# I2C.net
KiCad netlist of a schematic drawn in Altium Designer
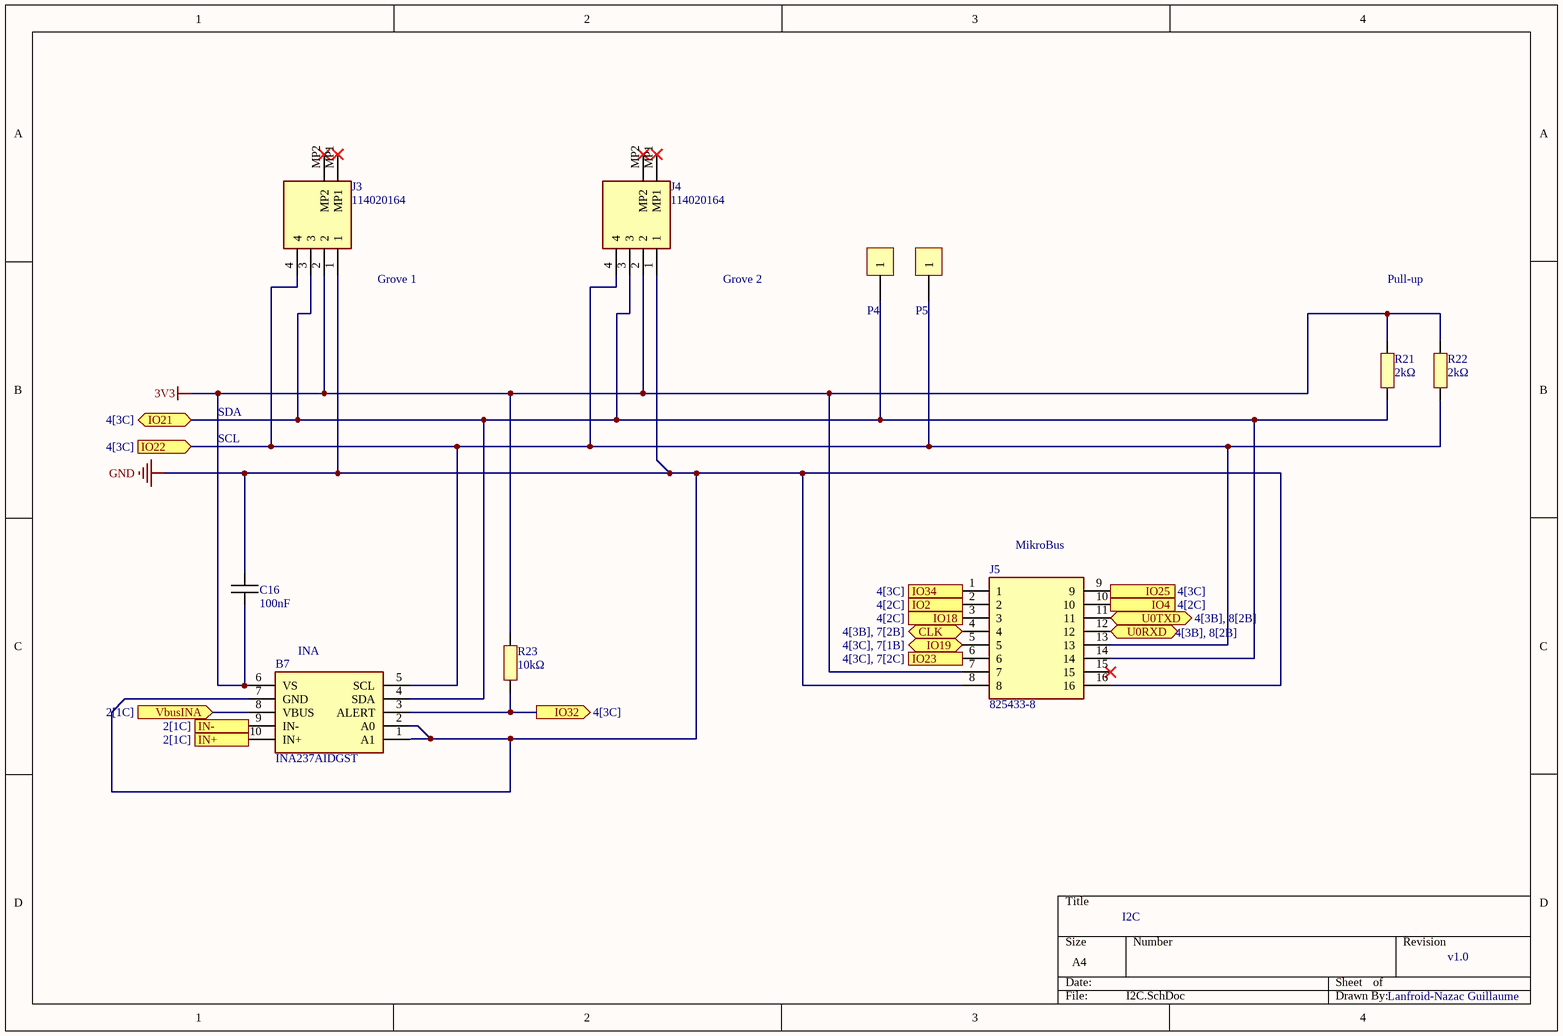
[diagram p0: I2C.SchDoc]

(export (version "E")
  (design (tool "Eeschema 10.0.6"))
  (components
    (comp (ref "B7")
      (value "INA237AIDGST")
      (footprint "SOP50P490X110-10N")
      (fields (field (name "MOUSER PART NUMBER") "595-INA237AIDGST"))
      (libsource (lib "SCHLibrary") (part "INA237AIDGST"))
    )
    (comp (ref "C16")
      (value "100nF")
      (footprint "CAPC1005X06N")
      (libsource (lib "SCHLibrary") (part "Capacitor"))
    )
    (comp (ref "J3")
      (value "114020164")
      (footprint "114020164")
      (description "Seeed Studio Accessories Grove Female Header - SMD-4P-2.0mm-90D-20Pcs")
      (fields (field (name "MOUSER PART NUMBER") "713-114020164"))
      (libsource (lib "SCHLibrary") (part "114020164"))
    )
    (comp (ref "J4")
      (value "114020164")
      (footprint "114020164")
      (description "Seeed Studio Accessories Grove Female Header - SMD-4P-2.0mm-90D-20Pcs")
      (fields (field (name "MOUSER PART NUMBER") "713-114020164"))
      (libsource (lib "SCHLibrary") (part "114020164"))
    )
    (comp (ref "J5")
      (value "825433-8")
      (footprint "Connect-Mikrobus")
      (description "Headers & Wire Housings 8P double for connection mikrobus")
      (fields (field (name "MOUSER PART NUMBER") "571-825433-8"))
      (libsource (lib "SCHLibrary") (part "Connect-Mikrobus"))
    )
    (comp (ref "P4")
      (value "Plage CMS 10x5")
      (footprint "Plage CMS 10x5")
      (description "Plage de report CMS 10x5mm")
      (libsource (lib "SCHLibrary") (part "Plage CMS 10x5"))
    )
    (comp (ref "P5")
      (value "Plage CMS 10x5")
      (footprint "Plage CMS 10x5")
      (description "Plage de report CMS 10x5mm")
      (libsource (lib "SCHLibrary") (part "Plage CMS 10x5"))
    )
    (comp (ref "R21")
      (value "2kΩ")
      (footprint "RESC1005X06N")
      (libsource (lib "SCHLibrary") (part "Resistor"))
    )
    (comp (ref "R22")
      (value "2kΩ")
      (footprint "RESC1005X06N")
      (libsource (lib "SCHLibrary") (part "Resistor"))
    )
    (comp (ref "R23")
      (value "10kΩ")
      (footprint "RESC1005X06N")
      (libsource (lib "SCHLibrary") (part "Resistor"))
    )
  )
  (nets
    (net (code "1") (name "/CLK") (class "Default")
      (node (ref "J5") (pin "4") (pinfunction "4_4") (pintype "passive"))
    )
    (net (code "2") (name "/IN+") (class "Default")
      (node (ref "B7") (pin "10") (pinfunction "IN+_10") (pintype "passive"))
    )
    (net (code "3") (name "/IN-") (class "Default")
      (node (ref "B7") (pin "9") (pinfunction "IN-_9") (pintype "passive"))
    )
    (net (code "4") (name "/IO2") (class "Default")
      (node (ref "J5") (pin "2") (pinfunction "2_2") (pintype "passive"))
    )
    (net (code "5") (name "/IO4") (class "Default")
      (node (ref "J5") (pin "10") (pinfunction "10_10") (pintype "passive"))
    )
    (net (code "6") (name "/IO18") (class "Default")
      (node (ref "J5") (pin "3") (pinfunction "3_3") (pintype "passive"))
    )
    (net (code "7") (name "/IO19") (class "Default")
      (node (ref "J5") (pin "5") (pinfunction "5_5") (pintype "passive"))
    )
    (net (code "8") (name "/IO21") (class "Default")
      (node (ref "B7") (pin "4") (pinfunction "SDA_4") (pintype "passive"))
      (node (ref "J3") (pin "3") (pinfunction "3_3") (pintype "passive"))
      (node (ref "J4") (pin "3") (pinfunction "3_3") (pintype "passive"))
      (node (ref "J5") (pin "14") (pinfunction "14_14") (pintype "passive"))
      (node (ref "P4") (pin "1") (pinfunction "1_1") (pintype "passive"))
      (node (ref "R21") (pin "2") (pinfunction "2_2") (pintype "passive"))
    )
    (net (code "9") (name "/IO22") (class "Default")
      (node (ref "B7") (pin "5") (pinfunction "SCL_5") (pintype "passive"))
      (node (ref "J3") (pin "4") (pinfunction "4_4") (pintype "passive"))
      (node (ref "J4") (pin "4") (pinfunction "4_4") (pintype "passive"))
      (node (ref "J5") (pin "13") (pinfunction "13_13") (pintype "passive"))
      (node (ref "P5") (pin "1") (pinfunction "1_1") (pintype "passive"))
      (node (ref "R22") (pin "2") (pinfunction "2_2") (pintype "passive"))
    )
    (net (code "10") (name "/IO23") (class "Default")
      (node (ref "J5") (pin "6") (pinfunction "6_6") (pintype "passive"))
    )
    (net (code "11") (name "/IO25") (class "Default")
      (node (ref "J5") (pin "9") (pinfunction "9_9") (pintype "passive"))
    )
    (net (code "12") (name "/IO32") (class "Default")
      (node (ref "B7") (pin "3") (pinfunction "ALERT_3") (pintype "passive"))
      (node (ref "R23") (pin "2") (pinfunction "2_2") (pintype "passive"))
    )
    (net (code "13") (name "/IO34") (class "Default")
      (node (ref "J5") (pin "1") (pinfunction "1_1") (pintype "passive"))
    )
    (net (code "14") (name "/U0RXD") (class "Default")
      (node (ref "J5") (pin "12") (pinfunction "12_12") (pintype "passive"))
    )
    (net (code "15") (name "/U0TXD") (class "Default")
      (node (ref "J5") (pin "11") (pinfunction "11_11") (pintype "passive"))
    )
    (net (code "16") (name "/VbusINA") (class "Default")
      (node (ref "B7") (pin "8") (pinfunction "VBUS_8") (pintype "passive"))
    )
    (net (code "17") (name "3V3") (class "Default")
      (node (ref "B7") (pin "6") (pinfunction "VS_6") (pintype "passive"))
      (node (ref "C16") (pin "1") (pinfunction "1_1") (pintype "passive"))
      (node (ref "J3") (pin "2") (pinfunction "2_2") (pintype "passive"))
      (node (ref "J4") (pin "2") (pinfunction "2_2") (pintype "passive"))
      (node (ref "J5") (pin "7") (pinfunction "7_7") (pintype "passive"))
      (node (ref "R21") (pin "1") (pinfunction "1_1") (pintype "passive"))
      (node (ref "R22") (pin "1") (pinfunction "1_1") (pintype "passive"))
      (node (ref "R23") (pin "1") (pinfunction "1_1") (pintype "passive"))
    )
    (net (code "18") (name "GND") (class "Default")
      (node (ref "B7") (pin "1") (pinfunction "A1_1") (pintype "passive"))
      (node (ref "B7") (pin "2") (pinfunction "A0_2") (pintype "passive"))
      (node (ref "B7") (pin "7") (pinfunction "GND_7") (pintype "passive"))
      (node (ref "C16") (pin "2") (pinfunction "2_2") (pintype "passive"))
      (node (ref "J3") (pin "1") (pinfunction "1_1") (pintype "passive"))
      (node (ref "J4") (pin "1") (pinfunction "1_1") (pintype "passive"))
      (node (ref "J5") (pin "16") (pinfunction "16_16") (pintype "passive"))
      (node (ref "J5") (pin "8") (pinfunction "8_8") (pintype "passive"))
    )
    (net (code "19") (name "unconnected-(J3-PadMP1)") (class "Default")
      (node (ref "J3") (pin "MP1") (pinfunction "MP1_MP1") (pintype "passive+no_connect"))
    )
    (net (code "20") (name "unconnected-(J3-PadMP2)") (class "Default")
      (node (ref "J3") (pin "MP2") (pinfunction "MP2_MP2") (pintype "passive+no_connect"))
    )
    (net (code "21") (name "unconnected-(J4-PadMP1)") (class "Default")
      (node (ref "J4") (pin "MP1") (pinfunction "MP1_MP1") (pintype "passive+no_connect"))
    )
    (net (code "22") (name "unconnected-(J4-PadMP2)") (class "Default")
      (node (ref "J4") (pin "MP2") (pinfunction "MP2_MP2") (pintype "passive+no_connect"))
    )
    (net (code "23") (name "unconnected-(J5-Pad15)") (class "Default")
      (node (ref "J5") (pin "15") (pinfunction "15_15") (pintype "passive+no_connect"))
    )
  )
)
